# polypointtritag.net
KiCad netlist of a schematic drawn in EAGLE
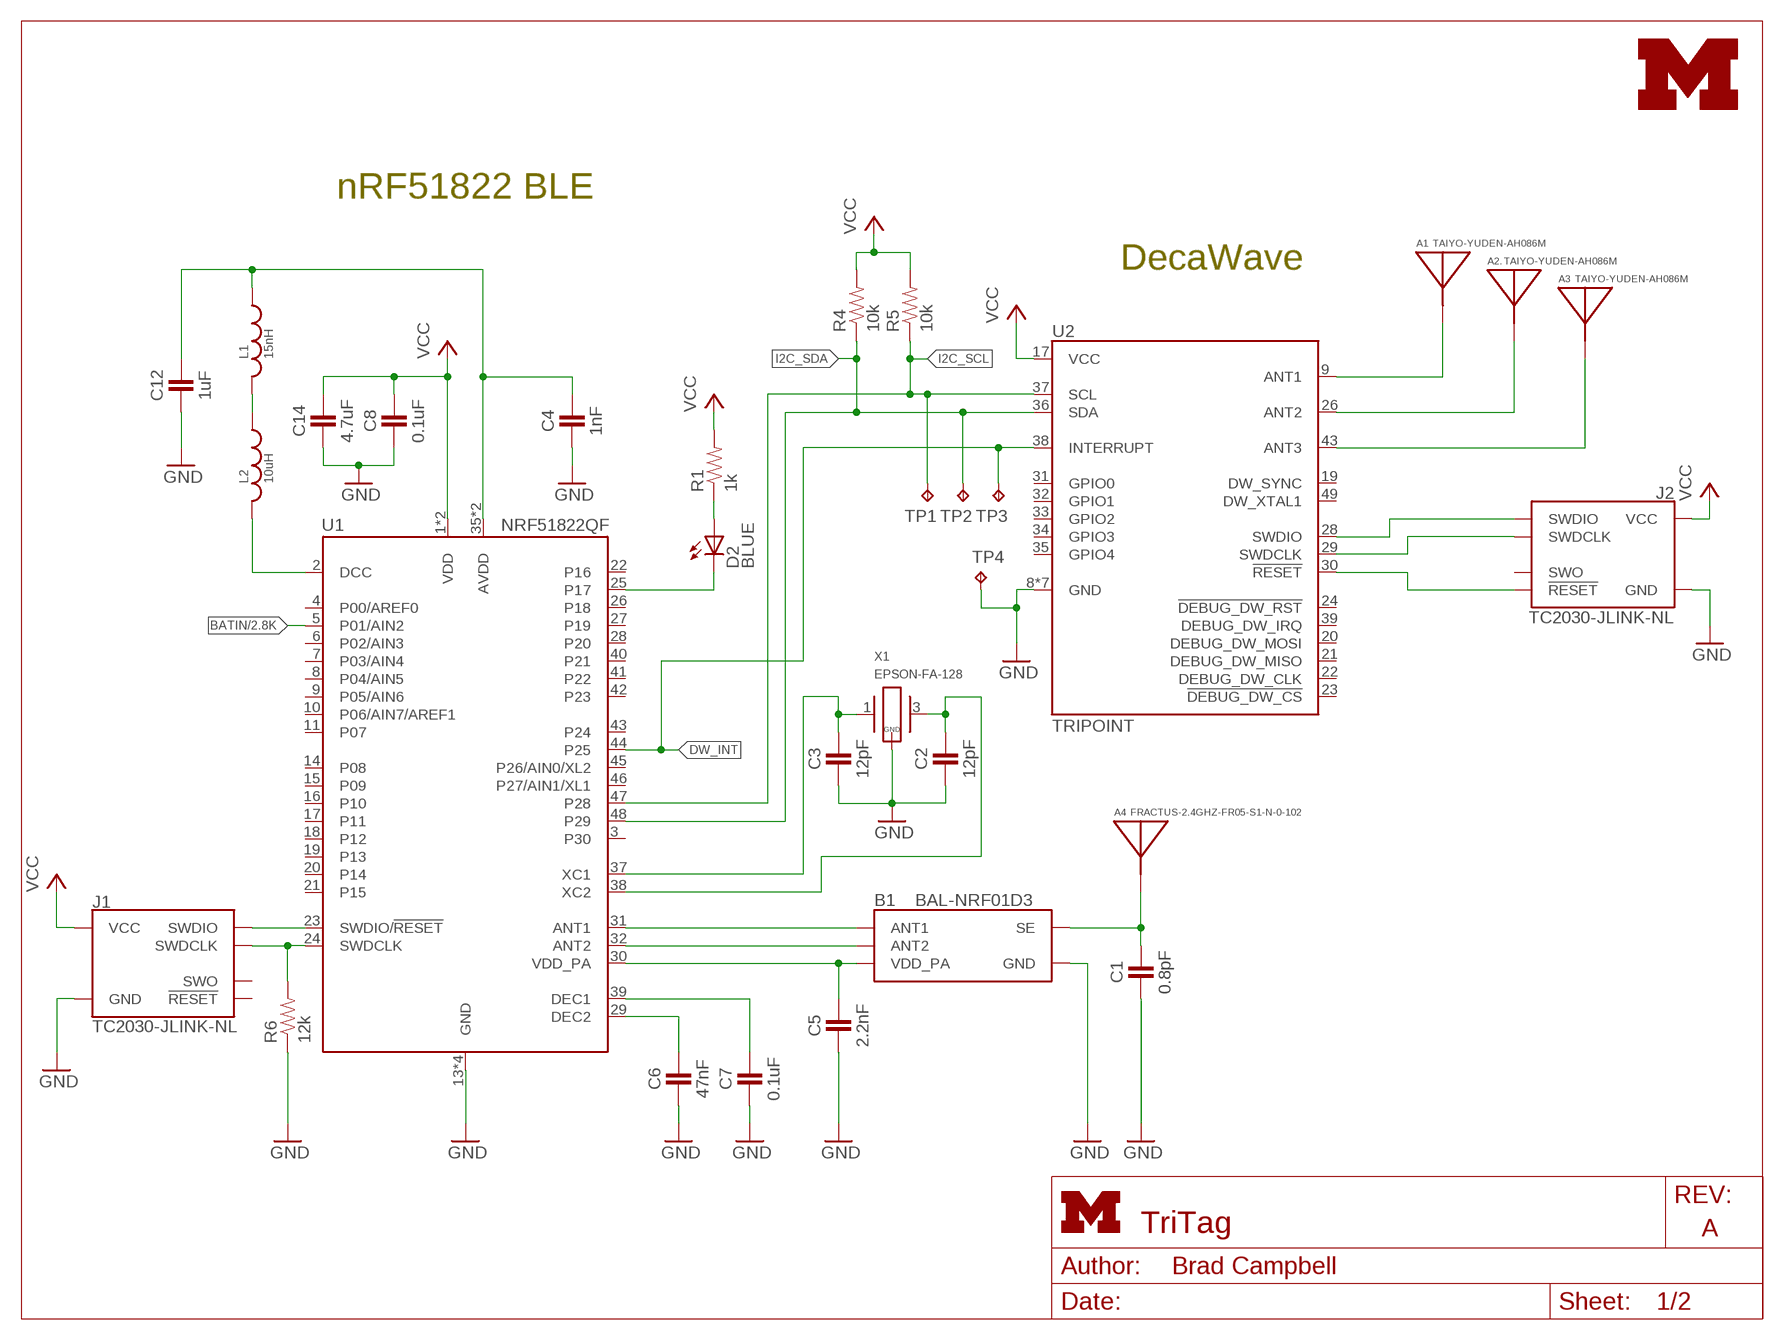
[diagram p0: schematic, sheet 1]
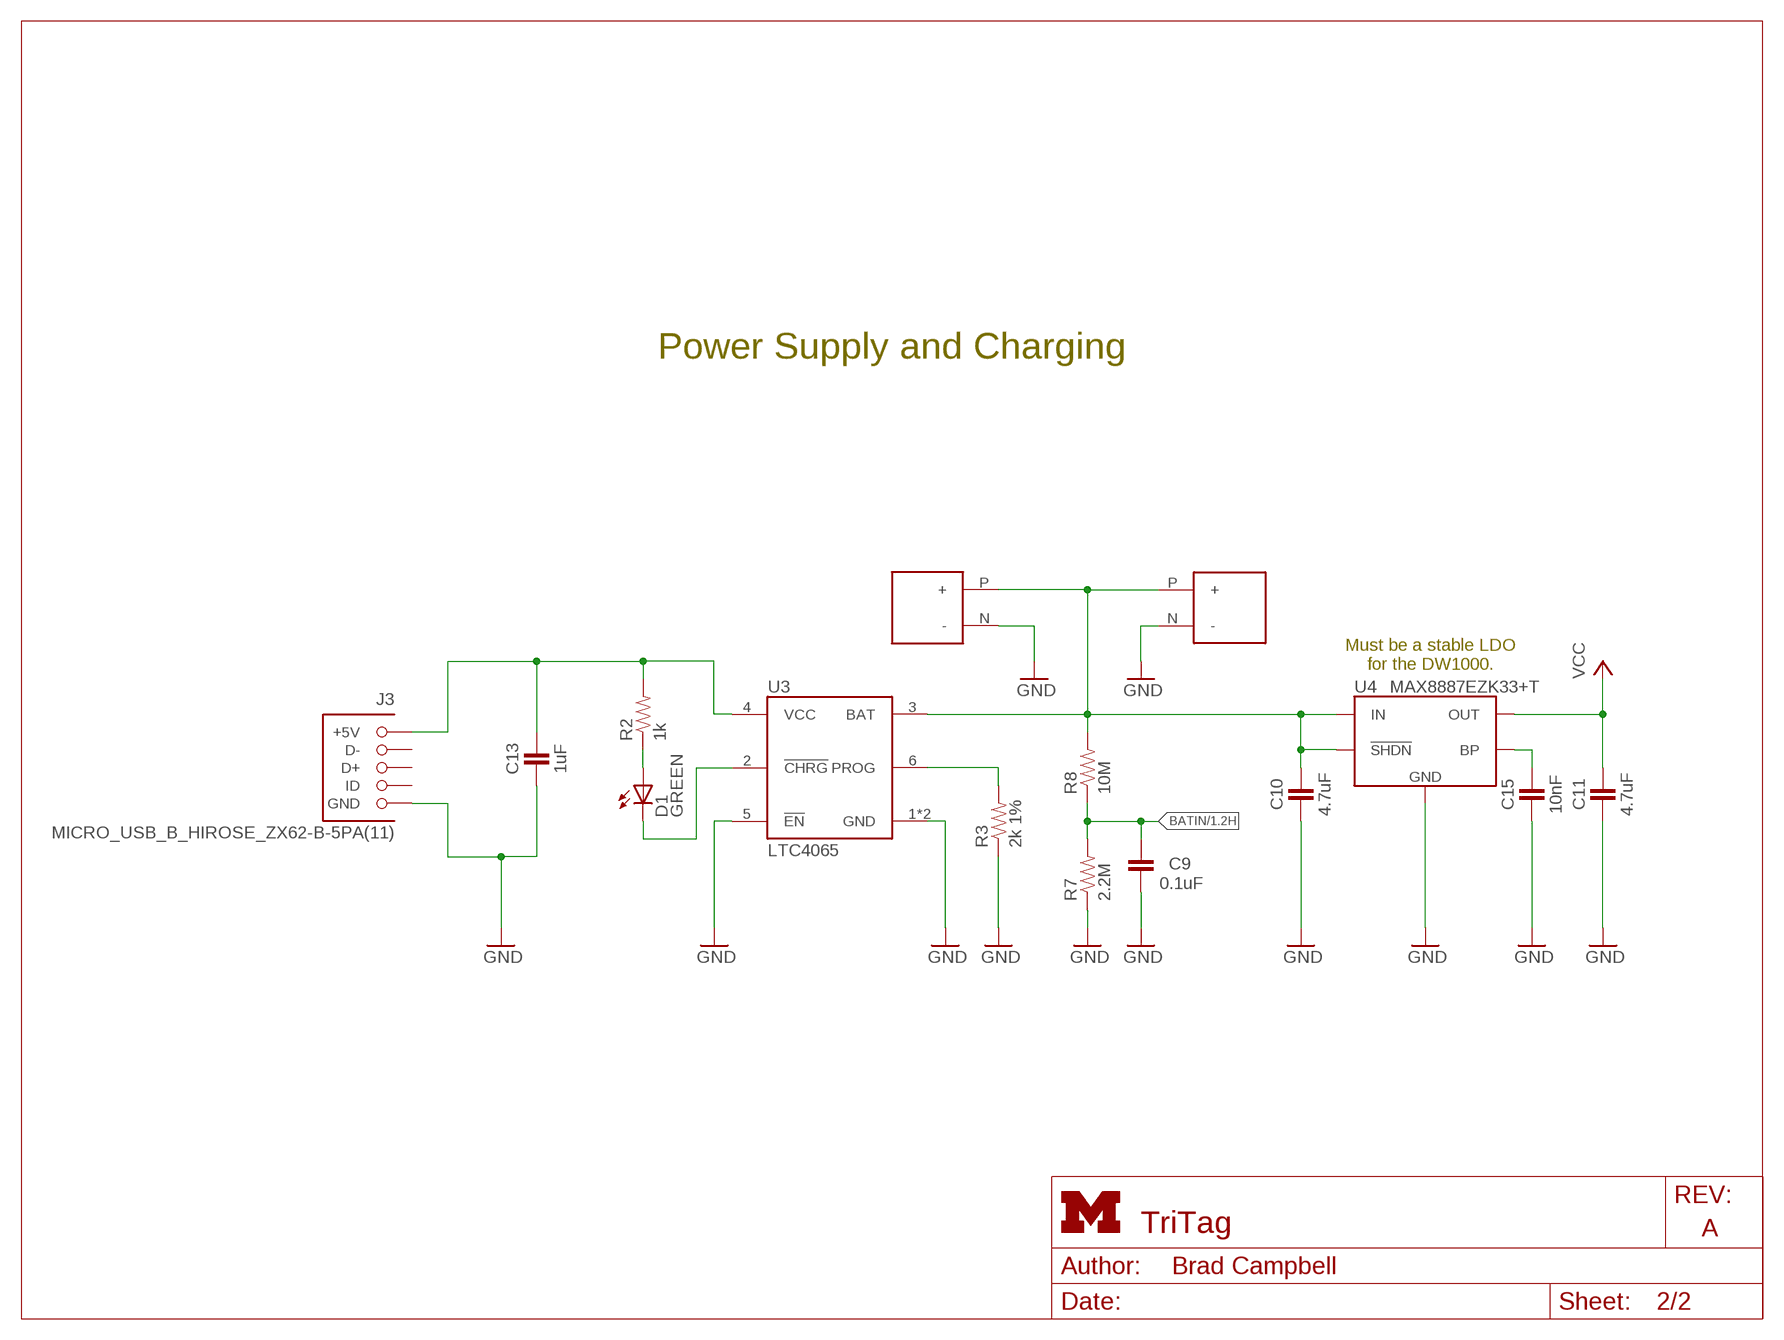
[diagram p1: schematic, sheet 2]

(export (version "E")
  (design (tool "Eeschema 10.0.6"))
  (components
    (comp (ref "A1")
      (value "TAIYO-YUDEN-AH086M")
      (footprint "eagle-import:TAIYO-YUDEN-AH086M")
      (libsource (lib "eagle-import") (part "TAIYO-YUDEN-AH086M"))
    )
    (comp (ref "A2.")
      (value "TAIYO-YUDEN-AH086M")
      (footprint "eagle-import:TAIYO-YUDEN-AH086M")
      (libsource (lib "eagle-import") (part "TAIYO-YUDEN-AH086M"))
    )
    (comp (ref "A3")
      (value "TAIYO-YUDEN-AH086M")
      (footprint "eagle-import:TAIYO-YUDEN-AH086M")
      (libsource (lib "eagle-import") (part "TAIYO-YUDEN-AH086M"))
    )
    (comp (ref "A4")
      (value "FRACTUS-2.4GHZ-FR05-S1-N-0-102")
      (footprint "eagle-import:FRACTUS-ANTENNA-FR05-S1-N-0-102")
      (libsource (lib "eagle-import") (part "FRACTUS-2.4GHZ-FR05-S1-N-0-102"))
    )
    (comp (ref "B1")
      (value "BAL-NRF01D3")
      (footprint "eagle-import:BAL-NRF01D3")
      (libsource (lib "eagle-import") (part "BAL-NRF01D3"))
    )
    (comp (ref "C1")
      (value "0.8pF")
      (footprint "eagle-import:0402_CAP")
      (libsource (lib "eagle-import") (part "CAPACITOR"))
    )
    (comp (ref "C2")
      (value "12pF")
      (footprint "eagle-import:0402_CAP")
      (libsource (lib "eagle-import") (part "CAPACITOR"))
    )
    (comp (ref "C3")
      (value "12pF")
      (footprint "eagle-import:0402_CAP")
      (libsource (lib "eagle-import") (part "CAPACITOR"))
    )
    (comp (ref "C4")
      (value "1nF")
      (footprint "eagle-import:0402_CAP")
      (libsource (lib "eagle-import") (part "CAPACITOR"))
    )
    (comp (ref "C5")
      (value "2.2nF")
      (footprint "eagle-import:0402_CAP")
      (libsource (lib "eagle-import") (part "CAPACITOR"))
    )
    (comp (ref "C6")
      (value "47nF")
      (footprint "eagle-import:0402_CAP")
      (libsource (lib "eagle-import") (part "CAPACITOR"))
    )
    (comp (ref "C7")
      (value "0.1uF")
      (footprint "eagle-import:0402_CAP")
      (libsource (lib "eagle-import") (part "CAPACITOR"))
    )
    (comp (ref "C8")
      (value "0.1uF")
      (footprint "eagle-import:0402_CAP")
      (libsource (lib "eagle-import") (part "CAPACITOR"))
    )
    (comp (ref "C12")
      (value "1uF")
      (footprint "eagle-import:0402_CAP")
      (libsource (lib "eagle-import") (part "CAPACITOR"))
    )
    (comp (ref "C14")
      (value "4.7uF")
      (footprint "eagle-import:0402_CAP")
      (libsource (lib "eagle-import") (part "CAPACITOR"))
    )
    (comp (ref "D2")
      (value "BLUE")
      (footprint "eagle-import:LED-0603")
      (libsource (lib "eagle-import") (part "LED0603"))
    )
    (comp (ref "J1")
      (value "TC2030-JLINK-NL")
      (footprint "eagle-import:TC2030-IDC-NL")
      (libsource (lib "eagle-import") (part "TC2030-JLINK-NL"))
    )
    (comp (ref "J2")
      (value "TC2030-JLINK-NL")
      (footprint "eagle-import:TC2030-IDC-NL")
      (libsource (lib "eagle-import") (part "TC2030-JLINK-NL"))
    )
    (comp (ref "L1")
      (value "15nH")
      (footprint "eagle-import:0402_CAP")
      (libsource (lib "eagle-import") (part "INDUCTOR0402"))
    )
    (comp (ref "L2")
      (value "10uH")
      (footprint "eagle-import:0603_CAP")
      (libsource (lib "eagle-import") (part "INDUCTOR0603"))
    )
    (comp (ref "LOGO1")
      (value "UMICH_SOLID_SMALL")
      (footprint "eagle-import:UMICH_SOLID_75MIL")
      (libsource (lib "eagle-import") (part "UMICH_SOLID_SMALL"))
    )
    (comp (ref "R1")
      (value "1k")
      (footprint "eagle-import:0402_RES")
      (libsource (lib "eagle-import") (part "RESISTOR0402_RES"))
    )
    (comp (ref "R4")
      (value "10k")
      (footprint "eagle-import:0402_RES")
      (libsource (lib "eagle-import") (part "RESISTOR0402_RES"))
    )
    (comp (ref "R5")
      (value "10k")
      (footprint "eagle-import:0402_RES")
      (libsource (lib "eagle-import") (part "RESISTOR0402_RES"))
    )
    (comp (ref "R6")
      (value "12k")
      (footprint "eagle-import:0402_RES")
      (libsource (lib "eagle-import") (part "RESISTOR0402_RES"))
    )
    (comp (ref "TP1")
      (value "TPTP06SQ")
      (footprint "eagle-import:TP06SQ")
      (libsource (lib "eagle-import") (part "TPTP06SQ"))
    )
    (comp (ref "TP2")
      (value "TPTP06SQ")
      (footprint "eagle-import:TP06SQ")
      (libsource (lib "eagle-import") (part "TPTP06SQ"))
    )
    (comp (ref "TP3")
      (value "TPTP06SQ")
      (footprint "eagle-import:TP06SQ")
      (libsource (lib "eagle-import") (part "TPTP06SQ"))
    )
    (comp (ref "TP4")
      (value "TPTP06SQ")
      (footprint "eagle-import:TP06SQ")
      (libsource (lib "eagle-import") (part "TPTP06SQ"))
    )
    (comp (ref "U1")
      (value "NRF51822QF")
      (footprint "eagle-import:QFN-48-6MM")
      (libsource (lib "eagle-import") (part "NRF51822QF"))
    )
    (comp (ref "U2")
      (value "TRIPOINT")
      (footprint "eagle-import:TRIPOINT")
      (libsource (lib "eagle-import") (part "TRIPOINT"))
    )
    (comp (ref "X1")
      (value "EPSON-FA-128")
      (footprint "eagle-import:FA-128")
      (libsource (lib "eagle-import") (part "EPSON-FA-128"))
    )
    (comp (ref "C9")
      (value "0.1uF")
      (footprint "eagle-import:0402_CAP")
      (libsource (lib "eagle-import") (part "CAPACITOR"))
    )
    (comp (ref "C10")
      (value "4.7uF")
      (footprint "eagle-import:0402_CAP")
      (libsource (lib "eagle-import") (part "CAPACITOR"))
    )
    (comp (ref "C11")
      (value "4.7uF")
      (footprint "eagle-import:0402_CAP")
      (libsource (lib "eagle-import") (part "CAPACITOR"))
    )
    (comp (ref "C13")
      (value "1uF")
      (footprint "eagle-import:0402_CAP")
      (libsource (lib "eagle-import") (part "CAPACITOR"))
    )
    (comp (ref "C15")
      (value "10nF")
      (footprint "eagle-import:0402_CAP")
      (libsource (lib "eagle-import") (part "CAPACITOR"))
    )
    (comp (ref "D1")
      (value "GREEN")
      (footprint "eagle-import:LED-0603")
      (libsource (lib "eagle-import") (part "LED0603"))
    )
    (comp (ref "J3")
      (value "MICRO_USB_B_HIROSE_ZX62-B-5PA(11)")
      (footprint "eagle-import:USB_MICRO_B-HIROSE-ZX62-B-5PA(11)")
      (libsource (lib "eagle-import") (part "MICRO_USB_B_HIROSE_ZX62-B-5PA(11)"))
    )
    (comp (ref "J4")
      (value "BAT_HOLE")
      (footprint "eagle-import:BATTERY_HOLE")
      (libsource (lib "eagle-import") (part "BAT_HOLE"))
    )
    (comp (ref "J5")
      (value "BAT_HOLE")
      (footprint "eagle-import:BATTERY_HOLE")
      (libsource (lib "eagle-import") (part "BAT_HOLE"))
    )
    (comp (ref "R2")
      (value "1k")
      (footprint "eagle-import:0402_RES")
      (libsource (lib "eagle-import") (part "RESISTOR0402_RES"))
    )
    (comp (ref "R3")
      (value "2k 1%")
      (footprint "eagle-import:0402_RES")
      (libsource (lib "eagle-import") (part "RESISTOR0402_RES"))
    )
    (comp (ref "R7")
      (value "2.2M")
      (footprint "eagle-import:0402_RES")
      (libsource (lib "eagle-import") (part "RESISTOR0402_RES"))
    )
    (comp (ref "R8")
      (value "10M")
      (footprint "eagle-import:0402_RES")
      (libsource (lib "eagle-import") (part "RESISTOR0402_RES"))
    )
    (comp (ref "U3")
      (value "LTC4065")
      (footprint "eagle-import:DFN-6_2MM")
      (libsource (lib "eagle-import") (part "LTC4065"))
    )
    (comp (ref "U4")
      (value "MAX8887EZK33+T")
      (footprint "eagle-import:SOT-23-5")
      (libsource (lib "eagle-import") (part "MAX8887EZK33+T"))
    )
  )
  (nets
    (net (code "1") (name "BATIN") (class "Default")
      (node (ref "C9") (pin "2") (pinfunction "2_2") (pintype "bidirectional"))
      (node (ref "R7") (pin "2") (pinfunction "2_2") (pintype "passive"))
      (node (ref "R8") (pin "1") (pinfunction "1_1") (pintype "passive"))
      (node (ref "U1") (pin "5") (pinfunction "P01/AIN2_5") (pintype "bidirectional"))
    )
    (net (code "2") (name "DW_INT") (class "Default")
      (node (ref "TP3") (pin "TP") (pinfunction "TP_TP") (pintype "input"))
      (node (ref "U1") (pin "44") (pinfunction "P25_44") (pintype "bidirectional"))
      (node (ref "U2") (pin "38") (pinfunction "INTERRUPT_38") (pintype "bidirectional"))
    )
    (net (code "3") (name "GND") (class "Default")
      (node (ref "B1") (pin "GND") (pinfunction "GND_GND") (pintype "bidirectional"))
      (node (ref "C1") (pin "2") (pinfunction "2_2") (pintype "bidirectional"))
      (node (ref "C10") (pin "2") (pinfunction "2_2") (pintype "bidirectional"))
      (node (ref "C11") (pin "2") (pinfunction "2_2") (pintype "bidirectional"))
      (node (ref "C12") (pin "2") (pinfunction "2_2") (pintype "bidirectional"))
      (node (ref "C13") (pin "2") (pinfunction "2_2") (pintype "bidirectional"))
      (node (ref "C14") (pin "2") (pinfunction "2_2") (pintype "bidirectional"))
      (node (ref "C15") (pin "2") (pinfunction "2_2") (pintype "bidirectional"))
      (node (ref "C2") (pin "2") (pinfunction "2_2") (pintype "bidirectional"))
      (node (ref "C3") (pin "2") (pinfunction "2_2") (pintype "bidirectional"))
      (node (ref "C4") (pin "2") (pinfunction "2_2") (pintype "bidirectional"))
      (node (ref "C5") (pin "2") (pinfunction "2_2") (pintype "bidirectional"))
      (node (ref "C6") (pin "2") (pinfunction "2_2") (pintype "bidirectional"))
      (node (ref "C7") (pin "2") (pinfunction "2_2") (pintype "bidirectional"))
      (node (ref "C8") (pin "2") (pinfunction "2_2") (pintype "bidirectional"))
      (node (ref "C9") (pin "1") (pinfunction "1_1") (pintype "bidirectional"))
      (node (ref "J1") (pin "5") (pinfunction "GND_5") (pintype "bidirectional"))
      (node (ref "J2") (pin "5") (pinfunction "GND_5") (pintype "bidirectional"))
      (node (ref "J3") (pin "5") (pinfunction "GND_5") (pintype "bidirectional"))
      (node (ref "J4") (pin "N") (pinfunction "-_N") (pintype "bidirectional"))
      (node (ref "J5") (pin "N") (pinfunction "-_N") (pintype "bidirectional"))
      (node (ref "R3") (pin "1") (pinfunction "1_1") (pintype "passive"))
      (node (ref "R6") (pin "1") (pinfunction "1_1") (pintype "passive"))
      (node (ref "R7") (pin "1") (pinfunction "1_1") (pintype "passive"))
      (node (ref "TP4") (pin "TP") (pinfunction "TP_TP") (pintype "input"))
      (node (ref "U1") (pin "13") (pinfunction "GND_13") (pintype "bidirectional"))
      (node (ref "U1") (pin "33") (pinfunction "GND_33") (pintype "bidirectional"))
      (node (ref "U1") (pin "34") (pinfunction "GND_34") (pintype "bidirectional"))
      (node (ref "U1") (pin "GND") (pinfunction "GND_GND") (pintype "bidirectional"))
      (node (ref "U2") (pin "10") (pinfunction "GND_10") (pintype "bidirectional"))
      (node (ref "U2") (pin "18") (pinfunction "GND_18") (pintype "bidirectional"))
      (node (ref "U2") (pin "25") (pinfunction "GND_25") (pintype "bidirectional"))
      (node (ref "U2") (pin "27") (pinfunction "GND_27") (pintype "bidirectional"))
      (node (ref "U2") (pin "42") (pinfunction "GND_42") (pintype "bidirectional"))
      (node (ref "U2") (pin "44") (pinfunction "GND_44") (pintype "bidirectional"))
      (node (ref "U2") (pin "8") (pinfunction "GND_8") (pintype "bidirectional"))
      (node (ref "U3") (pin "1") (pinfunction "GND_1") (pintype "bidirectional"))
      (node (ref "U3") (pin "5") (pinfunction "~{EN}_5") (pintype "bidirectional"))
      (node (ref "U3") (pin "7") (pinfunction "GND_7") (pintype "bidirectional"))
      (node (ref "U4") (pin "2") (pinfunction "GND_2") (pintype "bidirectional"))
      (node (ref "X1") (pin "2") (pinfunction "GND_2") (pintype "bidirectional"))
      (node (ref "X1") (pin "4") (pinfunction "GND_4") (pintype "bidirectional"))
    )
    (net (code "4") (name "I2C_SCL") (class "Default")
      (node (ref "R5") (pin "1") (pinfunction "1_1") (pintype "passive"))
      (node (ref "TP1") (pin "TP") (pinfunction "TP_TP") (pintype "input"))
      (node (ref "U1") (pin "47") (pinfunction "P28_47") (pintype "bidirectional"))
      (node (ref "U2") (pin "37") (pinfunction "SCL_37") (pintype "bidirectional"))
    )
    (net (code "5") (name "I2C_SDA") (class "Default")
      (node (ref "R4") (pin "1") (pinfunction "1_1") (pintype "passive"))
      (node (ref "TP2") (pin "TP") (pinfunction "TP_TP") (pintype "input"))
      (node (ref "U1") (pin "48") (pinfunction "P29_48") (pintype "bidirectional"))
      (node (ref "U2") (pin "36") (pinfunction "SDA_36") (pintype "bidirectional"))
    )
    (net (code "6") (name "Net-(A1-ANTENNA)") (class "Default")
      (node (ref "A1") (pin "A") (pinfunction "ANTENNA_A") (pintype "bidirectional"))
      (node (ref "U2") (pin "9") (pinfunction "ANT1_9") (pintype "bidirectional"))
    )
    (net (code "7") (name "Net-(A2.-ANTENNA)") (class "Default")
      (node (ref "A2.") (pin "A") (pinfunction "ANTENNA_A") (pintype "bidirectional"))
      (node (ref "U2") (pin "26") (pinfunction "ANT2_26") (pintype "bidirectional"))
    )
    (net (code "8") (name "Net-(A3-ANTENNA)") (class "Default")
      (node (ref "A3") (pin "A") (pinfunction "ANTENNA_A") (pintype "bidirectional"))
      (node (ref "U2") (pin "43") (pinfunction "ANT3_43") (pintype "bidirectional"))
    )
    (net (code "9") (name "Net-(A4-ANTENNA)") (class "Default")
      (node (ref "A4") (pin "1") (pinfunction "ANTENNA_1") (pintype "bidirectional"))
      (node (ref "B1") (pin "SE") (pinfunction "SE_SE") (pintype "bidirectional"))
      (node (ref "C1") (pin "1") (pinfunction "1_1") (pintype "bidirectional"))
    )
    (net (code "10") (name "Net-(B1-VDD_PA)") (class "Default")
      (node (ref "B1") (pin "VCC") (pinfunction "VDD_PA_VCC") (pintype "bidirectional"))
      (node (ref "C5") (pin "1") (pinfunction "1_1") (pintype "bidirectional"))
      (node (ref "U1") (pin "30") (pinfunction "VDD_PA_30") (pintype "bidirectional"))
    )
    (net (code "11") (name "Net-(C12-Pad1)") (class "Default")
      (node (ref "C12") (pin "1") (pinfunction "1_1") (pintype "bidirectional"))
      (node (ref "C4") (pin "1") (pinfunction "1_1") (pintype "bidirectional"))
      (node (ref "L1") (pin "1") (pinfunction "1_1") (pintype "bidirectional"))
      (node (ref "U1") (pin "35") (pinfunction "AVDD_35") (pintype "bidirectional"))
      (node (ref "U1") (pin "36") (pinfunction "AVDD_36") (pintype "bidirectional"))
    )
    (net (code "12") (name "Net-(D1-PadA)") (class "Default")
      (node (ref "D1") (pin "A") (pinfunction "A_A") (pintype "passive"))
      (node (ref "R2") (pin "1") (pinfunction "1_1") (pintype "passive"))
    )
    (net (code "13") (name "Net-(D2-PadA)") (class "Default")
      (node (ref "D2") (pin "A") (pinfunction "A_A") (pintype "passive"))
      (node (ref "R1") (pin "1") (pinfunction "1_1") (pintype "passive"))
    )
    (net (code "14") (name "Net-(J1-SWDCLK)") (class "Default")
      (node (ref "J1") (pin "4") (pinfunction "SWDCLK_4") (pintype "bidirectional"))
      (node (ref "R6") (pin "2") (pinfunction "2_2") (pintype "passive"))
      (node (ref "U1") (pin "24") (pinfunction "SWDCLK_24") (pintype "bidirectional"))
    )
    (net (code "15") (name "Net-(J1-SWDIO)") (class "Default")
      (node (ref "J1") (pin "2") (pinfunction "SWDIO_2") (pintype "bidirectional"))
      (node (ref "U1") (pin "23") (pinfunction "SWDIO/~{RESET}_23") (pintype "bidirectional"))
    )
    (net (code "16") (name "Net-(J2-SWDCLK)") (class "Default")
      (node (ref "J2") (pin "4") (pinfunction "SWDCLK_4") (pintype "bidirectional"))
      (node (ref "U2") (pin "29") (pinfunction "SWDCLK_29") (pintype "bidirectional"))
    )
    (net (code "17") (name "Net-(J2-SWDIO)") (class "Default")
      (node (ref "J2") (pin "2") (pinfunction "SWDIO_2") (pintype "bidirectional"))
      (node (ref "U2") (pin "28") (pinfunction "SWDIO_28") (pintype "bidirectional"))
    )
    (net (code "18") (name "Net-(J2-~{RESET})") (class "Default")
      (node (ref "J2") (pin "3") (pinfunction "~{RESET}_3") (pintype "bidirectional"))
      (node (ref "U2") (pin "30") (pinfunction "~{RESET}_30") (pintype "bidirectional"))
    )
    (net (code "19") (name "Net-(J3-+5V)") (class "Default")
      (node (ref "C13") (pin "1") (pinfunction "1_1") (pintype "bidirectional"))
      (node (ref "J3") (pin "1") (pinfunction "+5V_1") (pintype "bidirectional"))
      (node (ref "R2") (pin "2") (pinfunction "2_2") (pintype "passive"))
      (node (ref "U3") (pin "4") (pinfunction "VCC_4") (pintype "bidirectional"))
    )
    (net (code "20") (name "Net-(J4-+)") (class "Default")
      (node (ref "C10") (pin "1") (pinfunction "1_1") (pintype "bidirectional"))
      (node (ref "J4") (pin "P") (pinfunction "+_P") (pintype "bidirectional"))
      (node (ref "J5") (pin "P") (pinfunction "+_P") (pintype "bidirectional"))
      (node (ref "R8") (pin "2") (pinfunction "2_2") (pintype "passive"))
      (node (ref "U3") (pin "3") (pinfunction "BAT_3") (pintype "bidirectional"))
      (node (ref "U4") (pin "1") (pinfunction "IN_1") (pintype "bidirectional"))
      (node (ref "U4") (pin "3") (pinfunction "~{SHDN}_3") (pintype "bidirectional"))
    )
    (net (code "21") (name "Net-(L1-Pad2)") (class "Default")
      (node (ref "L1") (pin "2") (pinfunction "2_2") (pintype "bidirectional"))
      (node (ref "L2") (pin "1") (pinfunction "1_1") (pintype "bidirectional"))
    )
    (net (code "22") (name "Net-(U1-ANT1)") (class "Default")
      (node (ref "B1") (pin "ANT1") (pinfunction "ANT1_ANT1") (pintype "bidirectional"))
      (node (ref "U1") (pin "31") (pinfunction "ANT1_31") (pintype "bidirectional"))
    )
    (net (code "23") (name "Net-(U1-ANT2)") (class "Default")
      (node (ref "B1") (pin "ANT2") (pinfunction "ANT2_ANT2") (pintype "bidirectional"))
      (node (ref "U1") (pin "32") (pinfunction "ANT2_32") (pintype "bidirectional"))
    )
    (net (code "24") (name "Net-(U1-DCC)") (class "Default")
      (node (ref "L2") (pin "2") (pinfunction "2_2") (pintype "bidirectional"))
      (node (ref "U1") (pin "2") (pinfunction "DCC_2") (pintype "bidirectional"))
    )
    (net (code "25") (name "Net-(U1-DEC1)") (class "Default")
      (node (ref "C7") (pin "1") (pinfunction "1_1") (pintype "bidirectional"))
      (node (ref "U1") (pin "39") (pinfunction "DEC1_39") (pintype "bidirectional"))
    )
    (net (code "26") (name "Net-(U1-DEC2)") (class "Default")
      (node (ref "C6") (pin "1") (pinfunction "1_1") (pintype "bidirectional"))
      (node (ref "U1") (pin "29") (pinfunction "DEC2_29") (pintype "bidirectional"))
    )
    (net (code "27") (name "Net-(U1-P17)") (class "Default")
      (node (ref "D2") (pin "C") (pinfunction "C_C") (pintype "passive"))
      (node (ref "U1") (pin "25") (pinfunction "P17_25") (pintype "bidirectional"))
    )
    (net (code "28") (name "Net-(U1-XC1)") (class "Default")
      (node (ref "C3") (pin "1") (pinfunction "1_1") (pintype "bidirectional"))
      (node (ref "U1") (pin "37") (pinfunction "XC1_37") (pintype "bidirectional"))
      (node (ref "X1") (pin "1") (pinfunction "1_1") (pintype "bidirectional"))
    )
    (net (code "29") (name "Net-(U1-XC2)") (class "Default")
      (node (ref "C2") (pin "1") (pinfunction "1_1") (pintype "bidirectional"))
      (node (ref "U1") (pin "38") (pinfunction "XC2_38") (pintype "bidirectional"))
      (node (ref "X1") (pin "3") (pinfunction "2_3") (pintype "bidirectional"))
    )
    (net (code "30") (name "Net-(U3-PROG)") (class "Default")
      (node (ref "R3") (pin "2") (pinfunction "2_2") (pintype "passive"))
      (node (ref "U3") (pin "6") (pinfunction "PROG_6") (pintype "bidirectional"))
    )
    (net (code "31") (name "Net-(U3-~{CHRG})") (class "Default")
      (node (ref "D1") (pin "C") (pinfunction "C_C") (pintype "passive"))
      (node (ref "U3") (pin "2") (pinfunction "~{CHRG}_2") (pintype "bidirectional"))
    )
    (net (code "32") (name "Net-(U4-BP)") (class "Default")
      (node (ref "C15") (pin "1") (pinfunction "1_1") (pintype "bidirectional"))
      (node (ref "U4") (pin "4") (pinfunction "BP_4") (pintype "bidirectional"))
    )
    (net (code "33") (name "VCC") (class "Default")
      (node (ref "C11") (pin "1") (pinfunction "1_1") (pintype "bidirectional"))
      (node (ref "C14") (pin "1") (pinfunction "1_1") (pintype "bidirectional"))
      (node (ref "C8") (pin "1") (pinfunction "1_1") (pintype "bidirectional"))
      (node (ref "J1") (pin "1") (pinfunction "VCC_1") (pintype "bidirectional"))
      (node (ref "J2") (pin "1") (pinfunction "VCC_1") (pintype "bidirectional"))
      (node (ref "R1") (pin "2") (pinfunction "2_2") (pintype "passive"))
      (node (ref "R4") (pin "2") (pinfunction "2_2") (pintype "passive"))
      (node (ref "R5") (pin "2") (pinfunction "2_2") (pintype "passive"))
      (node (ref "U1") (pin "1") (pinfunction "VDD_1") (pintype "bidirectional"))
      (node (ref "U1") (pin "12") (pinfunction "VDD_12") (pintype "bidirectional"))
      (node (ref "U2") (pin "17") (pinfunction "VCC_17") (pintype "bidirectional"))
      (node (ref "U4") (pin "5") (pinfunction "OUT_5") (pintype "bidirectional"))
    )
    (net (code "34") (name "unconnected-(J1-SWO-Pad6)") (class "Default")
      (node (ref "J1") (pin "6") (pinfunction "SWO_6") (pintype "bidirectional"))
    )
    (net (code "35") (name "unconnected-(J1-~{RESET}-Pad3)") (class "Default")
      (node (ref "J1") (pin "3") (pinfunction "~{RESET}_3") (pintype "bidirectional"))
    )
    (net (code "36") (name "unconnected-(J2-SWO-Pad6)") (class "Default")
      (node (ref "J2") (pin "6") (pinfunction "SWO_6") (pintype "bidirectional"))
    )
    (net (code "37") (name "unconnected-(J3-D+-Pad3)") (class "Default")
      (node (ref "J3") (pin "3") (pinfunction "D+_3") (pintype "bidirectional"))
    )
    (net (code "38") (name "unconnected-(J3-D--Pad2)") (class "Default")
      (node (ref "J3") (pin "2") (pinfunction "D-_2") (pintype "bidirectional"))
    )
    (net (code "39") (name "unconnected-(J3-ID-Pad4)") (class "Default")
      (node (ref "J3") (pin "4") (pinfunction "ID_4") (pintype "bidirectional"))
    )
    (net (code "40") (name "unconnected-(U1-P00{slash}AREF0-Pad4)") (class "Default")
      (node (ref "U1") (pin "4") (pinfunction "P00/AREF0_4") (pintype "bidirectional"))
    )
    (net (code "41") (name "unconnected-(U1-P02{slash}AIN3-Pad6)") (class "Default")
      (node (ref "U1") (pin "6") (pinfunction "P02/AIN3_6") (pintype "bidirectional"))
    )
    (net (code "42") (name "unconnected-(U1-P03{slash}AIN4-Pad7)") (class "Default")
      (node (ref "U1") (pin "7") (pinfunction "P03/AIN4_7") (pintype "bidirectional"))
    )
    (net (code "43") (name "unconnected-(U1-P04{slash}AIN5-Pad8)") (class "Default")
      (node (ref "U1") (pin "8") (pinfunction "P04/AIN5_8") (pintype "bidirectional"))
    )
    (net (code "44") (name "unconnected-(U1-P05{slash}AIN6-Pad9)") (class "Default")
      (node (ref "U1") (pin "9") (pinfunction "P05/AIN6_9") (pintype "bidirectional"))
    )
    (net (code "45") (name "unconnected-(U1-P06{slash}AIN7{slash}AREF1-Pad10)") (class "Default")
      (node (ref "U1") (pin "10") (pinfunction "P06/AIN7/AREF1_10") (pintype "bidirectional"))
    )
    (net (code "46") (name "unconnected-(U1-P07-Pad11)") (class "Default")
      (node (ref "U1") (pin "11") (pinfunction "P07_11") (pintype "bidirectional"))
    )
    (net (code "47") (name "unconnected-(U1-P08-Pad14)") (class "Default")
      (node (ref "U1") (pin "14") (pinfunction "P08_14") (pintype "bidirectional"))
    )
    (net (code "48") (name "unconnected-(U1-P09-Pad15)") (class "Default")
      (node (ref "U1") (pin "15") (pinfunction "P09_15") (pintype "bidirectional"))
    )
    (net (code "49") (name "unconnected-(U1-P10-Pad16)") (class "Default")
      (node (ref "U1") (pin "16") (pinfunction "P10_16") (pintype "bidirectional"))
    )
    (net (code "50") (name "unconnected-(U1-P11-Pad17)") (class "Default")
      (node (ref "U1") (pin "17") (pinfunction "P11_17") (pintype "bidirectional"))
    )
    (net (code "51") (name "unconnected-(U1-P12-Pad18)") (class "Default")
      (node (ref "U1") (pin "18") (pinfunction "P12_18") (pintype "bidirectional"))
    )
    (net (code "52") (name "unconnected-(U1-P13-Pad19)") (class "Default")
      (node (ref "U1") (pin "19") (pinfunction "P13_19") (pintype "bidirectional"))
    )
    (net (code "53") (name "unconnected-(U1-P14-Pad20)") (class "Default")
      (node (ref "U1") (pin "20") (pinfunction "P14_20") (pintype "bidirectional"))
    )
    (net (code "54") (name "unconnected-(U1-P15-Pad21)") (class "Default")
      (node (ref "U1") (pin "21") (pinfunction "P15_21") (pintype "bidirectional"))
    )
    (net (code "55") (name "unconnected-(U1-P16-Pad22)") (class "Default")
      (node (ref "U1") (pin "22") (pinfunction "P16_22") (pintype "bidirectional"))
    )
    (net (code "56") (name "unconnected-(U1-P18-Pad26)") (class "Default")
      (node (ref "U1") (pin "26") (pinfunction "P18_26") (pintype "bidirectional"))
    )
    (net (code "57") (name "unconnected-(U1-P19-Pad27)") (class "Default")
      (node (ref "U1") (pin "27") (pinfunction "P19_27") (pintype "bidirectional"))
    )
    (net (code "58") (name "unconnected-(U1-P20-Pad28)") (class "Default")
      (node (ref "U1") (pin "28") (pinfunction "P20_28") (pintype "bidirectional"))
    )
    (net (code "59") (name "unconnected-(U1-P21-Pad40)") (class "Default")
      (node (ref "U1") (pin "40") (pinfunction "P21_40") (pintype "bidirectional"))
    )
    (net (code "60") (name "unconnected-(U1-P22-Pad41)") (class "Default")
      (node (ref "U1") (pin "41") (pinfunction "P22_41") (pintype "bidirectional"))
    )
    (net (code "61") (name "unconnected-(U1-P23-Pad42)") (class "Default")
      (node (ref "U1") (pin "42") (pinfunction "P23_42") (pintype "bidirectional"))
    )
    (net (code "62") (name "unconnected-(U1-P24-Pad43)") (class "Default")
      (node (ref "U1") (pin "43") (pinfunction "P24_43") (pintype "bidirectional"))
    )
    (net (code "63") (name "unconnected-(U1-P26{slash}AIN0{slash}XL2-Pad45)") (class "Default")
      (node (ref "U1") (pin "45") (pinfunction "P26/AIN0/XL2_45") (pintype "bidirectional"))
    )
    (net (code "64") (name "unconnected-(U1-P27{slash}AIN1{slash}XL1-Pad46)") (class "Default")
      (node (ref "U1") (pin "46") (pinfunction "P27/AIN1/XL1_46") (pintype "bidirectional"))
    )
    (net (code "65") (name "unconnected-(U1-P30-Pad3)") (class "Default")
      (node (ref "U1") (pin "3") (pinfunction "P30_3") (pintype "bidirectional"))
    )
    (net (code "66") (name "unconnected-(U2-DEBUG_DW_CLK-Pad22)") (class "Default")
      (node (ref "U2") (pin "22") (pinfunction "DEBUG_DW_CLK_22") (pintype "bidirectional"))
    )
    (net (code "67") (name "unconnected-(U2-DEBUG_DW_IRQ-Pad39)") (class "Default")
      (node (ref "U2") (pin "39") (pinfunction "DEBUG_DW_IRQ_39") (pintype "bidirectional"))
    )
    (net (code "68") (name "unconnected-(U2-DEBUG_DW_MISO-Pad21)") (class "Default")
      (node (ref "U2") (pin "21") (pinfunction "DEBUG_DW_MISO_21") (pintype "bidirectional"))
    )
    (net (code "69") (name "unconnected-(U2-DEBUG_DW_MOSI-Pad20)") (class "Default")
      (node (ref "U2") (pin "20") (pinfunction "DEBUG_DW_MOSI_20") (pintype "bidirectional"))
    )
    (net (code "70") (name "unconnected-(U2-DW_SYNC-Pad19)") (class "Default")
      (node (ref "U2") (pin "19") (pinfunction "DW_SYNC_19") (pintype "bidirectional"))
    )
    (net (code "71") (name "unconnected-(U2-DW_XTAL1-Pad49)") (class "Default")
      (node (ref "U2") (pin "49") (pinfunction "DW_XTAL1_49") (pintype "bidirectional"))
    )
    (net (code "72") (name "unconnected-(U2-GPIO0-Pad31)") (class "Default")
      (node (ref "U2") (pin "31") (pinfunction "GPIO0_31") (pintype "bidirectional"))
    )
    (net (code "73") (name "unconnected-(U2-GPIO1-Pad32)") (class "Default")
      (node (ref "U2") (pin "32") (pinfunction "GPIO1_32") (pintype "bidirectional"))
    )
    (net (code "74") (name "unconnected-(U2-GPIO2-Pad33)") (class "Default")
      (node (ref "U2") (pin "33") (pinfunction "GPIO2_33") (pintype "bidirectional"))
    )
    (net (code "75") (name "unconnected-(U2-GPIO3-Pad34)") (class "Default")
      (node (ref "U2") (pin "34") (pinfunction "GPIO3_34") (pintype "bidirectional"))
    )
    (net (code "76") (name "unconnected-(U2-GPIO4-Pad35)") (class "Default")
      (node (ref "U2") (pin "35") (pinfunction "GPIO4_35") (pintype "bidirectional"))
    )
    (net (code "77") (name "unconnected-(U2-~{DEBUG_DW_CS}-Pad23)") (class "Default")
      (node (ref "U2") (pin "23") (pinfunction "~{DEBUG_DW_CS}_23") (pintype "bidirectional"))
    )
    (net (code "78") (name "unconnected-(U2-~{DEBUG_DW_RST}-Pad24)") (class "Default")
      (node (ref "U2") (pin "24") (pinfunction "~{DEBUG_DW_RST}_24") (pintype "bidirectional"))
    )
  )
)
